# ADS1232.net
KiCad netlist of a schematic drawn in EAGLE
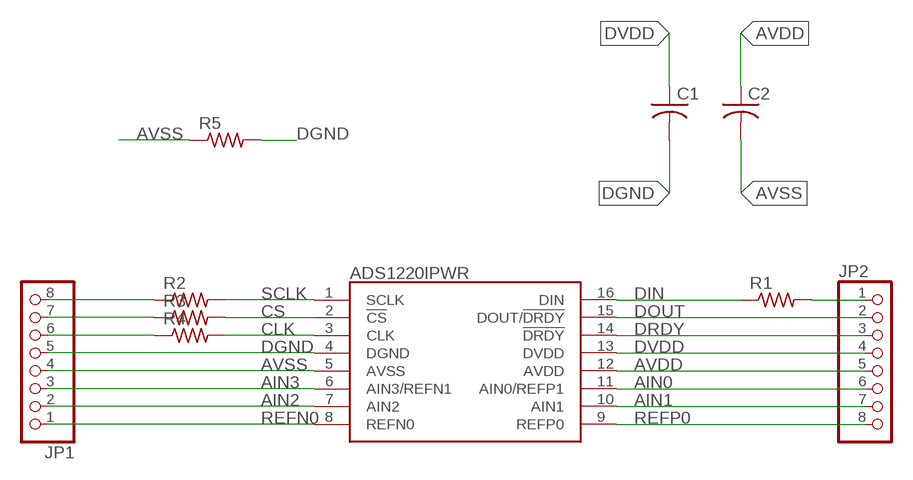
[diagram p0: schematic, sheet 1]

(export (version "E")
  (design (tool "Eeschema 10.0.6"))
  (components
    (comp (ref "C1")
      (value "C-USC0805K")
      (footprint "eagle-import:C0805K")
      (libsource (lib "eagle-import") (part "C-USC0805K"))
    )
    (comp (ref "C2")
      (value "C-USC0805K")
      (footprint "eagle-import:C0805K")
      (libsource (lib "eagle-import") (part "C-USC0805K"))
    )
    (comp (ref "IC1")
      (value "ADS1220IPWR")
      (footprint "eagle-import:SOP65P640X120-16N")
      (libsource (lib "eagle-import") (part "ADS1220IPWR"))
    )
    (comp (ref "JP1")
      (value "PINHD-1X8")
      (footprint "eagle-import:1X08")
      (libsource (lib "eagle-import") (part "PINHD-1X8"))
    )
    (comp (ref "JP2")
      (value "PINHD-1X8")
      (footprint "eagle-import:1X08")
      (libsource (lib "eagle-import") (part "PINHD-1X8"))
    )
    (comp (ref "R1")
      (value "R-US_M2012")
      (footprint "eagle-import:M2012")
      (libsource (lib "eagle-import") (part "R-US_M2012"))
    )
    (comp (ref "R2")
      (value "R-US_M2012")
      (footprint "eagle-import:M2012")
      (libsource (lib "eagle-import") (part "R-US_M2012"))
    )
    (comp (ref "R3")
      (value "R-US_M2012")
      (footprint "eagle-import:M2012")
      (libsource (lib "eagle-import") (part "R-US_M2012"))
    )
    (comp (ref "R4")
      (value "R-US_M2012")
      (footprint "eagle-import:M2012")
      (libsource (lib "eagle-import") (part "R-US_M2012"))
    )
    (comp (ref "R5")
      (value "R-US_M2012")
      (footprint "eagle-import:M2012")
      (libsource (lib "eagle-import") (part "R-US_M2012"))
    )
  )
  (nets
    (net (code "1") (name "/AIN0") (class "Default")
      (node (ref "IC1") (pin "11") (pinfunction "AIN0/REFP1_11") (pintype "bidirectional"))
      (node (ref "JP2") (pin "6") (pinfunction "6_6") (pintype "passive"))
    )
    (net (code "2") (name "/AIN1") (class "Default")
      (node (ref "IC1") (pin "10") (pinfunction "AIN1_10") (pintype "bidirectional"))
      (node (ref "JP2") (pin "7") (pinfunction "7_7") (pintype "passive"))
    )
    (net (code "3") (name "/AIN2") (class "Default")
      (node (ref "IC1") (pin "7") (pinfunction "AIN2_7") (pintype "bidirectional"))
      (node (ref "JP1") (pin "2") (pinfunction "2_2") (pintype "passive"))
    )
    (net (code "4") (name "/AIN3") (class "Default")
      (node (ref "IC1") (pin "6") (pinfunction "AIN3/REFN1_6") (pintype "bidirectional"))
      (node (ref "JP1") (pin "3") (pinfunction "3_3") (pintype "passive"))
    )
    (net (code "5") (name "/CLK") (class "Default")
      (node (ref "IC1") (pin "3") (pinfunction "CLK_3") (pintype "bidirectional"))
      (node (ref "R4") (pin "2") (pinfunction "2_2") (pintype "passive"))
    )
    (net (code "6") (name "/CS") (class "Default")
      (node (ref "IC1") (pin "2") (pinfunction "~{CS}_2") (pintype "bidirectional"))
      (node (ref "R3") (pin "2") (pinfunction "2_2") (pintype "passive"))
    )
    (net (code "7") (name "/DIN") (class "Default")
      (node (ref "IC1") (pin "16") (pinfunction "DIN_16") (pintype "bidirectional"))
      (node (ref "R1") (pin "1") (pinfunction "1_1") (pintype "passive"))
    )
    (net (code "8") (name "/DOUT") (class "Default")
      (node (ref "IC1") (pin "15") (pinfunction "DOUT/~{DRDY}_15") (pintype "bidirectional"))
      (node (ref "JP2") (pin "2") (pinfunction "2_2") (pintype "passive"))
    )
    (net (code "9") (name "/DRDY") (class "Default")
      (node (ref "IC1") (pin "14") (pinfunction "~{DRDY}_14") (pintype "bidirectional"))
      (node (ref "JP2") (pin "3") (pinfunction "3_3") (pintype "passive"))
    )
    (net (code "10") (name "/REFN0") (class "Default")
      (node (ref "IC1") (pin "8") (pinfunction "REFN0_8") (pintype "bidirectional"))
      (node (ref "JP1") (pin "1") (pinfunction "1_1") (pintype "passive"))
    )
    (net (code "11") (name "/REFP0") (class "Default")
      (node (ref "IC1") (pin "9") (pinfunction "REFP0_9") (pintype "bidirectional"))
      (node (ref "JP2") (pin "8") (pinfunction "8_8") (pintype "passive"))
    )
    (net (code "12") (name "/SCLK") (class "Default")
      (node (ref "IC1") (pin "1") (pinfunction "SCLK_1") (pintype "bidirectional"))
      (node (ref "R2") (pin "2") (pinfunction "2_2") (pintype "passive"))
    )
    (net (code "13") (name "AVDD") (class "Default")
      (node (ref "C2") (pin "1") (pinfunction "1_1") (pintype "passive"))
      (node (ref "IC1") (pin "12") (pinfunction "AVDD_12") (pintype "bidirectional"))
      (node (ref "JP2") (pin "5") (pinfunction "5_5") (pintype "passive"))
    )
    (net (code "14") (name "AVSS") (class "Default")
      (node (ref "C2") (pin "2") (pinfunction "2_2") (pintype "passive"))
      (node (ref "IC1") (pin "5") (pinfunction "AVSS_5") (pintype "bidirectional"))
      (node (ref "JP1") (pin "4") (pinfunction "4_4") (pintype "passive"))
      (node (ref "R5") (pin "1") (pinfunction "1_1") (pintype "passive"))
    )
    (net (code "15") (name "DGND") (class "Default")
      (node (ref "C1") (pin "2") (pinfunction "2_2") (pintype "passive"))
      (node (ref "IC1") (pin "4") (pinfunction "DGND_4") (pintype "bidirectional"))
      (node (ref "JP1") (pin "5") (pinfunction "5_5") (pintype "passive"))
      (node (ref "R5") (pin "2") (pinfunction "2_2") (pintype "passive"))
    )
    (net (code "16") (name "DVDD") (class "Default")
      (node (ref "C1") (pin "1") (pinfunction "1_1") (pintype "passive"))
      (node (ref "IC1") (pin "13") (pinfunction "DVDD_13") (pintype "bidirectional"))
      (node (ref "JP2") (pin "4") (pinfunction "4_4") (pintype "passive"))
    )
    (net (code "17") (name "Net-(JP1-Pad6)") (class "Default")
      (node (ref "JP1") (pin "6") (pinfunction "6_6") (pintype "passive"))
      (node (ref "R4") (pin "1") (pinfunction "1_1") (pintype "passive"))
    )
    (net (code "18") (name "Net-(JP1-Pad7)") (class "Default")
      (node (ref "JP1") (pin "7") (pinfunction "7_7") (pintype "passive"))
      (node (ref "R3") (pin "1") (pinfunction "1_1") (pintype "passive"))
    )
    (net (code "19") (name "Net-(JP1-Pad8)") (class "Default")
      (node (ref "JP1") (pin "8") (pinfunction "8_8") (pintype "passive"))
      (node (ref "R2") (pin "1") (pinfunction "1_1") (pintype "passive"))
    )
    (net (code "20") (name "Net-(JP2-Pad1)") (class "Default")
      (node (ref "JP2") (pin "1") (pinfunction "1_1") (pintype "passive"))
      (node (ref "R1") (pin "2") (pinfunction "2_2") (pintype "passive"))
    )
  )
)
